# 15_-_LED-User-Debug.net
KiCad netlist of a schematic drawn in Altium Designer
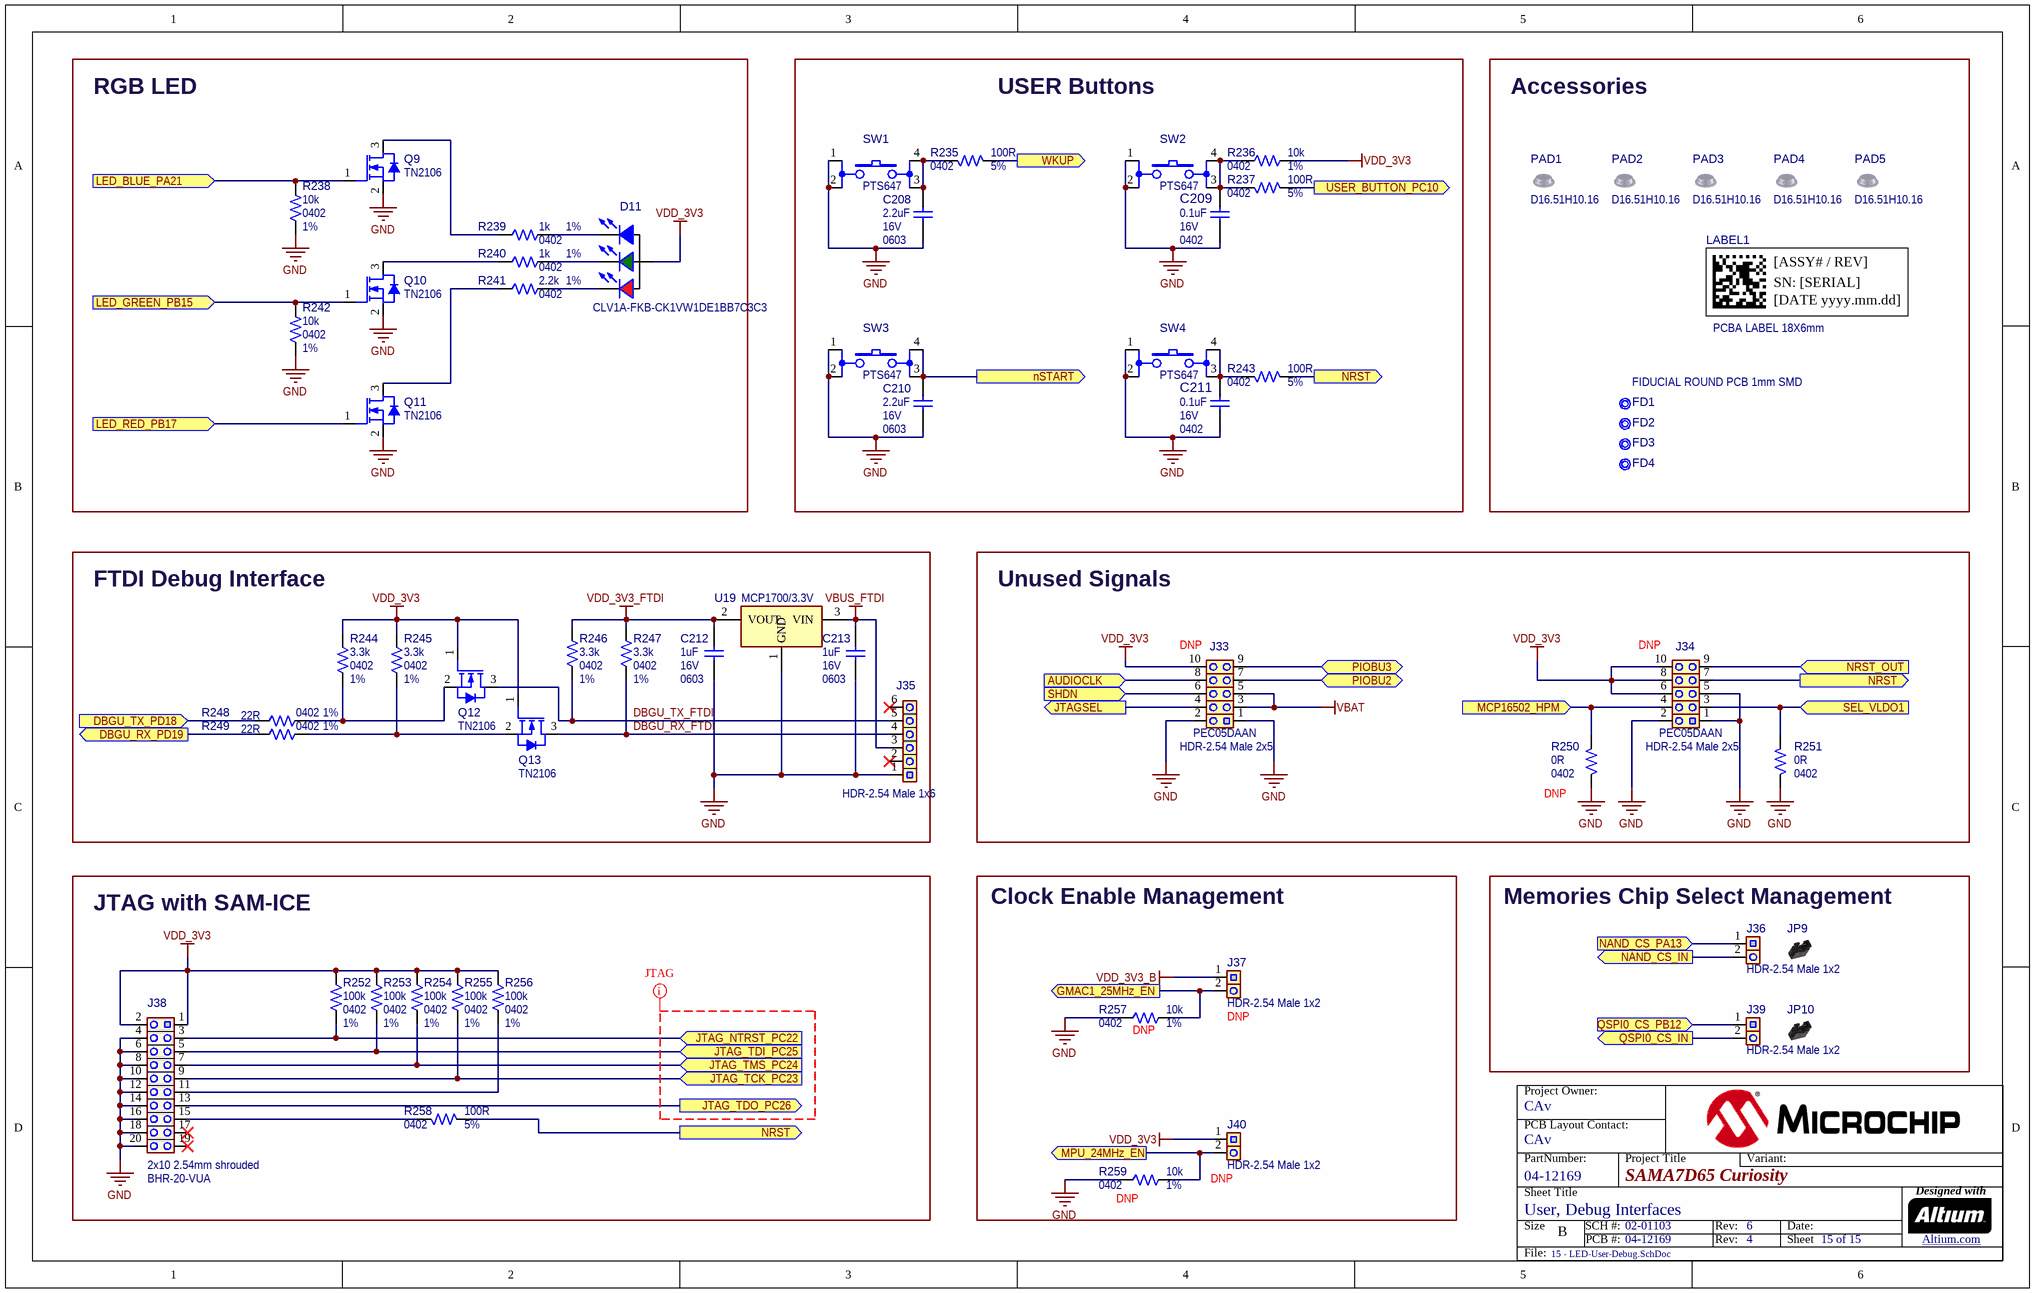
[diagram p0: 15 - LED-User-Debug.SchDoc]

(export (version "E")
  (design (tool "Eeschema 10.0.6"))
  (components
    (comp (ref "C208")
      (value "2.2uF")
      (footprint "CAP_C_0603")
      (fields
        (field (name "VOLTAGE") "16V")
        (field (name "PACKAGE") "0603")
        (field (name "TOLERANCE") "10%")
        (field (name "Comment") "Capacitor NP")
      )
      (libsource (lib "MCHP-CDB") (part "Capacitor NP"))
    )
    (comp (ref "C209")
      (value "0.1uF")
      (footprint "CAP_C_0402")
      (fields
        (field (name "VOLTAGE") "16V")
        (field (name "PACKAGE") "0402")
        (field (name "TOLERANCE") "10%")
        (field (name "Comment") "Capacitor NP")
        (field (name "OWNER") "Sompoch Loboonlert")
      )
      (libsource (lib "MCHP-CDB") (part "Capacitor NP"))
    )
    (comp (ref "C210")
      (value "2.2uF")
      (footprint "CAP_C_0603")
      (fields
        (field (name "VOLTAGE") "16V")
        (field (name "PACKAGE") "0603")
        (field (name "TOLERANCE") "10%")
        (field (name "Comment") "Capacitor NP")
      )
      (libsource (lib "MCHP-CDB") (part "Capacitor NP"))
    )
    (comp (ref "C211")
      (value "0.1uF")
      (footprint "CAP_C_0402")
      (fields
        (field (name "VOLTAGE") "16V")
        (field (name "PACKAGE") "0402")
        (field (name "TOLERANCE") "10%")
        (field (name "Comment") "Capacitor NP")
        (field (name "OWNER") "Sompoch Loboonlert")
      )
      (libsource (lib "MCHP-CDB") (part "Capacitor NP"))
    )
    (comp (ref "C212")
      (value "1uF")
      (footprint "CAP_C_0603")
      (fields
        (field (name "VOLTAGE") "16V")
        (field (name "PACKAGE") "0603")
        (field (name "TOLERANCE") "10%")
        (field (name "Comment") "Capacitor NP")
      )
      (libsource (lib "MCHP-CDB") (part "Capacitor NP"))
    )
    (comp (ref "C213")
      (value "1uF")
      (footprint "CAP_C_0603")
      (fields
        (field (name "VOLTAGE") "16V")
        (field (name "PACKAGE") "0603")
        (field (name "TOLERANCE") "10%")
        (field (name "Comment") "Capacitor NP")
      )
      (libsource (lib "MCHP-CDB") (part "Capacitor NP"))
    )
    (comp (ref "D11")
      (value "LED_RGB_CLV1A")
      (footprint "PLCC-4_CLV1A-FKB")
      (fields
        (field (name "POWER") "130mW, 100mW, 100mW")
        (field (name "MANUFACTURER PART NUMBER 1") "CLV1A-FKB-CK1VW1DE1BB7C3C3")
        (field (name "OWNER") "Randolph Sobrepena")
      )
      (libsource (lib "MCHP-CDB") (part "LED_RGB_CLV1A"))
    )
    (comp (ref "FD1")
      (value "FIDUCIAL ROUND")
      (footprint "Fiducial_1mm")
      (description "Fiducial")
      (fields
        (field (name "DESCRIPTION_") "FIDUCIAL ROUND PCB 1mm SMD")
        (field (name "OWNER") "Dragos Danaila")
      )
      (libsource (lib "MCHP-CDB") (part "FIDUCIAL ROUND"))
    )
    (comp (ref "FD2")
      (value "FIDUCIAL ROUND")
      (footprint "Fiducial_1mm")
      (description "Fiducial")
      (fields (field (name "OWNER") "Dragos Danaila"))
      (libsource (lib "MCHP-CDB") (part "FIDUCIAL ROUND"))
    )
    (comp (ref "FD3")
      (value "FIDUCIAL ROUND")
      (footprint "Fiducial_1mm")
      (description "Fiducial")
      (fields (field (name "OWNER") "Dragos Danaila"))
      (libsource (lib "MCHP-CDB") (part "FIDUCIAL ROUND"))
    )
    (comp (ref "FD4")
      (value "FIDUCIAL ROUND")
      (footprint "Fiducial_1mm")
      (description "Fiducial")
      (fields (field (name "OWNER") "Dragos Danaila"))
      (libsource (lib "MCHP-CDB") (part "FIDUCIAL ROUND"))
    )
    (comp (ref "J33")
      (value "HDR-2.54 Male 2x5")
      (footprint "HDR_M_2.54_2x5")
      (fields
        (field (name "MANUFACTURER PART NUMBER 1") "PEC05DAAN")
        (field (name "POPULATED") "DNP")
        (field (name "Comment") "Header 2x5")
        (field (name "OWNER") "Mike Sullivan (Arena)")
      )
      (libsource (lib "MCHP-CDB") (part "Header 2x5"))
    )
    (comp (ref "J34")
      (value "HDR-2.54 Male 2x5")
      (footprint "HDR_M_2.54_2x5")
      (fields
        (field (name "MANUFACTURER PART NUMBER 1") "PEC05DAAN")
        (field (name "POPULATED") "DNP")
        (field (name "Comment") "Header 2x5")
        (field (name "OWNER") "Mike Sullivan (Arena)")
      )
      (libsource (lib "MCHP-CDB") (part "Header 2x5"))
    )
    (comp (ref "J35")
      (value "HDR-2.54 Male 1x6")
      (footprint "HDR_M_2.54_1x6")
      (fields (field (name "Comment") "Header 1x6") (field (name "OWNER") "Bogdan P (M91398)"))
      (libsource (lib "MCHP-CDB") (part "Header 1x6"))
    )
    (comp (ref "J36")
      (value "HDR-2.54 Male 1x2")
      (footprint "HDR_M_2.54_1x2")
      (fields
        (field (name "VOLTAGE") "250V")
        (field (name "Comment") "Header 1x2")
        (field (name "OWNER") "Narasimha Murthy")
      )
      (libsource (lib "MCHP-CDB") (part "Header 1x2"))
    )
    (comp (ref "J37")
      (value "HDR-2.54 Male 1x2")
      (footprint "HDR_M_2.54_1x2")
      (fields
        (field (name "POPULATED") "DNP")
        (field (name "VOLTAGE") "250V")
        (field (name "Comment") "Header 1x2")
        (field (name "OWNER") "Narasimha Murthy")
      )
      (libsource (lib "MCHP-CDB") (part "Header 1x2"))
    )
    (comp (ref "J38")
      (value "2x10 2.54mm shrouded")
      (footprint "HDR_M_2.54_2X10_SBH11-PBPC-D10-ST-BK")
      (fields
        (field (name "MANUFACTURER PART NUMBER 1") "BHR-20-VUA")
        (field (name "VOLTAGE") "250VAC")
        (field (name "Comment") "Header 2x10")
        (field (name "OWNER") "Dragos Danaila")
      )
      (libsource (lib "MCHP-CDB") (part "Header 2x10"))
    )
    (comp (ref "J39")
      (value "HDR-2.54 Male 1x2")
      (footprint "HDR_M_2.54_1x2")
      (fields
        (field (name "VOLTAGE") "250V")
        (field (name "Comment") "Header 1x2")
        (field (name "OWNER") "Narasimha Murthy")
      )
      (libsource (lib "MCHP-CDB") (part "Header 1x2"))
    )
    (comp (ref "J40")
      (value "HDR-2.54 Male 1x2")
      (footprint "HDR_M_2.54_1x2")
      (fields
        (field (name "POPULATED") "DNP")
        (field (name "VOLTAGE") "250V")
        (field (name "Comment") "Header 1x2")
        (field (name "OWNER") "Narasimha Murthy")
      )
      (libsource (lib "MCHP-CDB") (part "Header 1x2"))
    )
    (comp (ref "JP9")
      (value "Jumper Mechanical")
      (footprint "Jumper_Mechanical")
      (fields (field (name "OWNER") "Narasimha Murthy"))
      (libsource (lib "MCHP-CDB") (part "Jumper Mechanical"))
    )
    (comp (ref "JP10")
      (value "Jumper Mechanical")
      (footprint "Jumper_Mechanical")
      (fields (field (name "OWNER") "Narasimha Murthy"))
      (libsource (lib "MCHP-CDB") (part "Jumper Mechanical"))
    )
    (comp (ref "LABEL1")
      (value "PCBA LABEL 18X6mm")
      (footprint "08-10015")
      (fields (field (name "Comment") "08-10015") (field (name "OWNER") "Mark Loper"))
      (libsource (lib "MCHP-CDB") (part "08-10015"))
    )
    (comp (ref "PAD1")
      (value "D16.51H10.16")
      (footprint "BUMP_BUMPERSPECIALTIES_BS11BL04X08RP_CYLINDRICAL_BLACK_D16.51H10.16")
      (fields (field (name "Comment") "Rubber Pad Cylindrical Taper") (field (name "OWNER") "Dragos Danaila"))
      (libsource (lib "MCHP-CDB") (part "Rubber Pad Cylindrical Taper"))
    )
    (comp (ref "PAD2")
      (value "D16.51H10.16")
      (footprint "BUMP_BUMPERSPECIALTIES_BS11BL04X08RP_CYLINDRICAL_BLACK_D16.51H10.16")
      (fields (field (name "Comment") "Rubber Pad Cylindrical Taper") (field (name "OWNER") "Dragos Danaila"))
      (libsource (lib "MCHP-CDB") (part "Rubber Pad Cylindrical Taper"))
    )
    (comp (ref "PAD3")
      (value "D16.51H10.16")
      (footprint "BUMP_BUMPERSPECIALTIES_BS11BL04X08RP_CYLINDRICAL_BLACK_D16.51H10.16")
      (fields (field (name "Comment") "Rubber Pad Cylindrical Taper") (field (name "OWNER") "Dragos Danaila"))
      (libsource (lib "MCHP-CDB") (part "Rubber Pad Cylindrical Taper"))
    )
    (comp (ref "PAD4")
      (value "D16.51H10.16")
      (footprint "BUMP_BUMPERSPECIALTIES_BS11BL04X08RP_CYLINDRICAL_BLACK_D16.51H10.16")
      (fields (field (name "Comment") "Rubber Pad Cylindrical Taper") (field (name "OWNER") "Dragos Danaila"))
      (libsource (lib "MCHP-CDB") (part "Rubber Pad Cylindrical Taper"))
    )
    (comp (ref "PAD5")
      (value "D16.51H10.16")
      (footprint "BUMP_BUMPERSPECIALTIES_BS11BL04X08RP_CYLINDRICAL_BLACK_D16.51H10.16")
      (fields (field (name "Comment") "Rubber Pad Cylindrical Taper") (field (name "OWNER") "Dragos Danaila"))
      (libsource (lib "MCHP-CDB") (part "Rubber Pad Cylindrical Taper"))
    )
    (comp (ref "Q9")
      (value "TN2106")
      (footprint "SOT-23-3")
      (description "Transistor MOS")
      (fields (field (name "Comment") "Transistor MOS-N GSD") (field (name "OWNER") "Ilie Galan"))
      (libsource (lib "MCHP-CDB") (part "Transistor MOS-N GSD"))
    )
    (comp (ref "Q10")
      (value "TN2106")
      (footprint "SOT-23-3")
      (description "Transistor MOS")
      (fields (field (name "Comment") "Transistor MOS-N GSD") (field (name "OWNER") "Ilie Galan"))
      (libsource (lib "MCHP-CDB") (part "Transistor MOS-N GSD"))
    )
    (comp (ref "Q11")
      (value "TN2106")
      (footprint "SOT-23-3")
      (description "Transistor MOS")
      (fields (field (name "Comment") "Transistor MOS-N GSD") (field (name "OWNER") "Ilie Galan"))
      (libsource (lib "MCHP-CDB") (part "Transistor MOS-N GSD"))
    )
    (comp (ref "Q12")
      (value "TN2106")
      (footprint "SOT-23-3")
      (description "Transistor MOS")
      (fields (field (name "Comment") "Transistor MOS-N GSD") (field (name "OWNER") "Ilie Galan"))
      (libsource (lib "MCHP-CDB") (part "Transistor MOS-N GSD"))
    )
    (comp (ref "Q13")
      (value "TN2106")
      (footprint "SOT-23-3")
      (description "Transistor MOS")
      (fields (field (name "Comment") "Transistor MOS-N GSD") (field (name "OWNER") "Ilie Galan"))
      (libsource (lib "MCHP-CDB") (part "Transistor MOS-N GSD"))
    )
    (comp (ref "R235")
      (value "100R")
      (footprint "RES_C_0402")
      (description "Resistor")
      (fields
        (field (name "PACKAGE") "0402")
        (field (name "TOLERANCE") "5%")
        (field (name "VOLTAGE") "50V")
        (field (name "POWER") "1/16W")
        (field (name "OWNER") "Dragos Danaila")
      )
      (libsource (lib "MCHP-CDB") (part "Resistor"))
    )
    (comp (ref "R236")
      (value "10k")
      (footprint "RES_C_0402")
      (description "Resistor")
      (fields
        (field (name "PACKAGE") "0402")
        (field (name "TOLERANCE") "1%")
        (field (name "POWER") "1/10W")
        (field (name "VOLTAGE") "50V")
        (field (name "OWNER") "Brent Lanphear")
      )
      (libsource (lib "MCHP-CDB") (part "Resistor"))
    )
    (comp (ref "R237")
      (value "100R")
      (footprint "RES_C_0402")
      (description "Resistor")
      (fields
        (field (name "PACKAGE") "0402")
        (field (name "TOLERANCE") "5%")
        (field (name "VOLTAGE") "50V")
        (field (name "POWER") "1/16W")
        (field (name "OWNER") "Dragos Danaila")
      )
      (libsource (lib "MCHP-CDB") (part "Resistor"))
    )
    (comp (ref "R238")
      (value "10k")
      (footprint "RES_C_0402")
      (description "Resistor")
      (fields
        (field (name "PACKAGE") "0402")
        (field (name "TOLERANCE") "1%")
        (field (name "POWER") "1/10W")
        (field (name "VOLTAGE") "50V")
        (field (name "OWNER") "Brent Lanphear")
      )
      (libsource (lib "MCHP-CDB") (part "Resistor"))
    )
    (comp (ref "R239")
      (value "1k")
      (footprint "RES_C_0402")
      (description "Resistor")
      (fields
        (field (name "PACKAGE") "0402")
        (field (name "TOLERANCE") "1%")
        (field (name "VOLTAGE") "50V")
        (field (name "POWER") "1/10W")
        (field (name "OWNER") "Tad Ahlvers")
      )
      (libsource (lib "") (part "Resistor_1"))
    )
    (comp (ref "R240")
      (value "1k")
      (footprint "RES_C_0402")
      (description "Resistor")
      (fields
        (field (name "PACKAGE") "0402")
        (field (name "TOLERANCE") "1%")
        (field (name "VOLTAGE") "50V")
        (field (name "POWER") "1/10W")
        (field (name "OWNER") "Tad Ahlvers")
      )
      (libsource (lib "") (part "Resistor_1"))
    )
    (comp (ref "R241")
      (value "2.2k")
      (footprint "RES_C_0402")
      (description "Resistor")
      (fields
        (field (name "PACKAGE") "0402")
        (field (name "TOLERANCE") "1%")
        (field (name "VOLTAGE") "50V")
        (field (name "POWER") "1/10W")
        (field (name "OWNER") "Tad Ahlvers")
      )
      (libsource (lib "MCHP-CDB") (part "Resistor"))
    )
    (comp (ref "R242")
      (value "10k")
      (footprint "RES_C_0402")
      (description "Resistor")
      (fields
        (field (name "PACKAGE") "0402")
        (field (name "TOLERANCE") "1%")
        (field (name "POWER") "1/10W")
        (field (name "VOLTAGE") "50V")
        (field (name "OWNER") "Brent Lanphear")
      )
      (libsource (lib "MCHP-CDB") (part "Resistor"))
    )
    (comp (ref "R243")
      (value "100R")
      (footprint "RES_C_0402")
      (description "Resistor")
      (fields
        (field (name "PACKAGE") "0402")
        (field (name "TOLERANCE") "5%")
        (field (name "VOLTAGE") "50V")
        (field (name "POWER") "1/16W")
        (field (name "OWNER") "Dragos Danaila")
      )
      (libsource (lib "MCHP-CDB") (part "Resistor"))
    )
    (comp (ref "R244")
      (value "3.3k")
      (footprint "RES_C_0402")
      (description "Resistor")
      (fields
        (field (name "PACKAGE") "0402")
        (field (name "TOLERANCE") "1%")
        (field (name "VOLTAGE") "50V")
        (field (name "POWER") "1/10W")
        (field (name "OWNER") "Mike Ragsdale")
      )
      (libsource (lib "MCHP-CDB") (part "Resistor"))
    )
    (comp (ref "R245")
      (value "3.3k")
      (footprint "RES_C_0402")
      (description "Resistor")
      (fields
        (field (name "PACKAGE") "0402")
        (field (name "TOLERANCE") "1%")
        (field (name "VOLTAGE") "50V")
        (field (name "POWER") "1/10W")
        (field (name "OWNER") "Mike Ragsdale")
      )
      (libsource (lib "MCHP-CDB") (part "Resistor"))
    )
    (comp (ref "R246")
      (value "3.3k")
      (footprint "RES_C_0402")
      (description "Resistor")
      (fields
        (field (name "PACKAGE") "0402")
        (field (name "TOLERANCE") "1%")
        (field (name "VOLTAGE") "50V")
        (field (name "POWER") "1/10W")
        (field (name "OWNER") "Mike Ragsdale")
      )
      (libsource (lib "MCHP-CDB") (part "Resistor"))
    )
    (comp (ref "R247")
      (value "3.3k")
      (footprint "RES_C_0402")
      (description "Resistor")
      (fields
        (field (name "PACKAGE") "0402")
        (field (name "TOLERANCE") "1%")
        (field (name "VOLTAGE") "50V")
        (field (name "POWER") "1/10W")
        (field (name "OWNER") "Mike Ragsdale")
      )
      (libsource (lib "MCHP-CDB") (part "Resistor"))
    )
    (comp (ref "R248")
      (value "22R")
      (footprint "RES_C_0402")
      (description "Resistor")
      (fields
        (field (name "PACKAGE") "0402")
        (field (name "TOLERANCE") "1%")
        (field (name "POWER") "1/10W")
        (field (name "OWNER") "Mike Ragsdale")
      )
      (libsource (lib "MCHP-CDB") (part "Resistor"))
    )
    (comp (ref "R249")
      (value "22R")
      (footprint "RES_C_0402")
      (description "Resistor")
      (fields
        (field (name "PACKAGE") "0402")
        (field (name "TOLERANCE") "1%")
        (field (name "POWER") "1/10W")
        (field (name "OWNER") "Mike Ragsdale")
      )
      (libsource (lib "MCHP-CDB") (part "Resistor"))
    )
    (comp (ref "R250")
      (value "0R")
      (footprint "RES_C_0402")
      (description "Resistor")
      (fields
        (field (name "PACKAGE") "0402")
        (field (name "POWER") "1/16W")
        (field (name "POPULATED") "DNP")
        (field (name "OWNER") "Sompoch Loboonlert")
      )
      (libsource (lib "") (part "Resistor_1"))
    )
    (comp (ref "R251")
      (value "0R")
      (footprint "RES_C_0402")
      (description "Resistor")
      (fields
        (field (name "PACKAGE") "0402")
        (field (name "POWER") "1/16W")
        (field (name "OWNER") "Sompoch Loboonlert")
      )
      (libsource (lib "") (part "Resistor_1"))
    )
    (comp (ref "R252")
      (value "100k")
      (footprint "RES_C_0402")
      (description "Resistor")
      (fields
        (field (name "PACKAGE") "0402")
        (field (name "TOLERANCE") "1%")
        (field (name "VOLTAGE") "50V")
        (field (name "POWER") "1/10W")
        (field (name "OWNER") "Tad Ahlvers")
      )
      (libsource (lib "MCHP-CDB") (part "Resistor"))
    )
    (comp (ref "R253")
      (value "100k")
      (footprint "RES_C_0402")
      (description "Resistor")
      (fields
        (field (name "PACKAGE") "0402")
        (field (name "TOLERANCE") "1%")
        (field (name "VOLTAGE") "50V")
        (field (name "POWER") "1/10W")
        (field (name "OWNER") "Tad Ahlvers")
      )
      (libsource (lib "MCHP-CDB") (part "Resistor"))
    )
    (comp (ref "R254")
      (value "100k")
      (footprint "RES_C_0402")
      (description "Resistor")
      (fields
        (field (name "PACKAGE") "0402")
        (field (name "TOLERANCE") "1%")
        (field (name "VOLTAGE") "50V")
        (field (name "POWER") "1/10W")
        (field (name "OWNER") "Tad Ahlvers")
      )
      (libsource (lib "MCHP-CDB") (part "Resistor"))
    )
    (comp (ref "R255")
      (value "100k")
      (footprint "RES_C_0402")
      (description "Resistor")
      (fields
        (field (name "PACKAGE") "0402")
        (field (name "TOLERANCE") "1%")
        (field (name "VOLTAGE") "50V")
        (field (name "POWER") "1/10W")
        (field (name "OWNER") "Tad Ahlvers")
      )
      (libsource (lib "MCHP-CDB") (part "Resistor"))
    )
    (comp (ref "R256")
      (value "100k")
      (footprint "RES_C_0402")
      (description "Resistor")
      (fields
        (field (name "PACKAGE") "0402")
        (field (name "TOLERANCE") "1%")
        (field (name "VOLTAGE") "50V")
        (field (name "POWER") "1/10W")
        (field (name "OWNER") "Tad Ahlvers")
      )
      (libsource (lib "MCHP-CDB") (part "Resistor"))
    )
    (comp (ref "R257")
      (value "10k")
      (footprint "RES_C_0402")
      (description "Resistor")
      (fields
        (field (name "PACKAGE") "0402")
        (field (name "TOLERANCE") "1%")
        (field (name "VOLTAGE") "50V")
        (field (name "POWER") "1/10W")
        (field (name "POPULATED") "DNP")
        (field (name "OWNER") "Brent Lanphear")
      )
      (libsource (lib "") (part "Resistor_1"))
    )
    (comp (ref "R258")
      (value "100R")
      (footprint "RES_C_0402")
      (description "Resistor")
      (fields
        (field (name "PACKAGE") "0402")
        (field (name "TOLERANCE") "5%")
        (field (name "VOLTAGE") "50V")
        (field (name "POWER") "1/16W")
        (field (name "OWNER") "Dragos Danaila")
      )
      (libsource (lib "MCHP-CDB") (part "Resistor"))
    )
    (comp (ref "R259")
      (value "10k")
      (footprint "RES_C_0402")
      (description "Resistor")
      (fields
        (field (name "PACKAGE") "0402")
        (field (name "TOLERANCE") "1%")
        (field (name "VOLTAGE") "50V")
        (field (name "POWER") "1/10W")
        (field (name "POPULATED") "DNP")
        (field (name "OWNER") "Brent Lanphear")
      )
      (libsource (lib "") (part "Resistor_1"))
    )
    (comp (ref "SW1")
      (value "PTS647")
      (footprint "SW_SMD_4.5mmX4.5mm_PTS647")
      (description "Switch")
      (fields
        (field (name "VOLTAGE") "12V")
        (field (name "Comment") "Switch 4 Pin")
        (field (name "OWNER") "Dragos Danaila")
      )
      (libsource (lib "MCHP-CDB") (part "Switch 4 Pin"))
    )
    (comp (ref "SW2")
      (value "PTS647")
      (footprint "SW_SMD_4.5mmX4.5mm_PTS647")
      (description "Switch")
      (fields
        (field (name "VOLTAGE") "12V")
        (field (name "Comment") "Switch 4 Pin")
        (field (name "OWNER") "Dragos Danaila")
      )
      (libsource (lib "MCHP-CDB") (part "Switch 4 Pin"))
    )
    (comp (ref "SW3")
      (value "PTS647")
      (footprint "SW_SMD_4.5mmX4.5mm_PTS647")
      (description "Switch")
      (fields
        (field (name "VOLTAGE") "12V")
        (field (name "Comment") "Switch 4 Pin")
        (field (name "OWNER") "Dragos Danaila")
      )
      (libsource (lib "MCHP-CDB") (part "Switch 4 Pin"))
    )
    (comp (ref "SW4")
      (value "PTS647")
      (footprint "SW_SMD_4.5mmX4.5mm_PTS647")
      (description "Switch")
      (fields
        (field (name "VOLTAGE") "12V")
        (field (name "Comment") "Switch 4 Pin")
        (field (name "OWNER") "Dragos Danaila")
      )
      (libsource (lib "MCHP-CDB") (part "Switch 4 Pin"))
    )
    (comp (ref "U19")
      (value "MCP1700/3.3V")
      (footprint "SOT-23-3")
      (description "LDO")
      (fields (field (name "Comment") "MCP170X SOT-23-3_SOT-23A-3"))
      (libsource (lib "MCHP-CDB") (part "MCP170X SOT-23-3_SOT-23A-3"))
    )
  )
  (nets
    (net (code "1") (name "/AUDIOCLK") (class "Default")
      (node (ref "J33") (pin "8") (pinfunction "8_8") (pintype "passive"))
    )
    (net (code "2") (name "/DBGU_RX_FTDI") (class "Default")
      (node (ref "J35") (pin "4") (pinfunction "4_4") (pintype "passive"))
      (node (ref "Q13") (pin "3") (pinfunction "D_3") (pintype "passive"))
      (node (ref "R247") (pin "1") (pinfunction "1_1") (pintype "passive"))
    )
    (net (code "3") (name "/DBGU_RX_PD19") (class "Default")
      (node (ref "R249") (pin "1") (pinfunction "1_1") (pintype "passive"))
    )
    (net (code "4") (name "/DBGU_TX_FTDI") (class "Default")
      (node (ref "J35") (pin "5") (pinfunction "5_5") (pintype "passive"))
      (node (ref "Q12") (pin "3") (pinfunction "D_3") (pintype "passive"))
      (node (ref "R246") (pin "1") (pinfunction "1_1") (pintype "passive"))
    )
    (net (code "5") (name "/DBGU_TX_PD18") (class "Default")
      (node (ref "R248") (pin "1") (pinfunction "1_1") (pintype "passive"))
    )
    (net (code "6") (name "/GMAC1_25MHz_EN") (class "Default")
      (node (ref "J37") (pin "2") (pinfunction "2_2") (pintype "passive"))
      (node (ref "R257") (pin "1") (pinfunction "1_1") (pintype "passive"))
    )
    (net (code "7") (name "/JTAGSEL") (class "Default")
      (node (ref "J33") (pin "4") (pinfunction "4_4") (pintype "passive"))
    )
    (net (code "8") (name "/JTAG_NTRST_PC22") (class "Default")
      (node (ref "J38") (pin "3") (pinfunction "3_3") (pintype "passive"))
      (node (ref "R252") (pin "1") (pinfunction "1_1") (pintype "passive"))
    )
    (net (code "9") (name "/JTAG_TCK_PC23") (class "Default")
      (node (ref "J38") (pin "9") (pinfunction "9_9") (pintype "passive"))
      (node (ref "R255") (pin "1") (pinfunction "1_1") (pintype "passive"))
    )
    (net (code "10") (name "/JTAG_TDI_PC25") (class "Default")
      (node (ref "J38") (pin "5") (pinfunction "5_5") (pintype "passive"))
      (node (ref "R253") (pin "1") (pinfunction "1_1") (pintype "passive"))
    )
    (net (code "11") (name "/JTAG_TDO_PC26") (class "Default")
      (node (ref "J38") (pin "13") (pinfunction "13_13") (pintype "passive"))
    )
    (net (code "12") (name "/JTAG_TMS_PC24") (class "Default")
      (node (ref "J38") (pin "7") (pinfunction "7_7") (pintype "passive"))
      (node (ref "R254") (pin "1") (pinfunction "1_1") (pintype "passive"))
    )
    (net (code "13") (name "/LED_BLUE_PA21") (class "Default")
      (node (ref "Q9") (pin "1") (pinfunction "G_1") (pintype "passive"))
      (node (ref "R238") (pin "1") (pinfunction "1_1") (pintype "passive"))
    )
    (net (code "14") (name "/LED_GREEN_PB15") (class "Default")
      (node (ref "Q10") (pin "1") (pinfunction "G_1") (pintype "passive"))
      (node (ref "R242") (pin "1") (pinfunction "1_1") (pintype "passive"))
    )
    (net (code "15") (name "/LED_RED_PB17") (class "Default")
      (node (ref "Q11") (pin "1") (pinfunction "G_1") (pintype "passive"))
    )
    (net (code "16") (name "/MCP16502_HPM") (class "Default")
      (node (ref "J34") (pin "4") (pinfunction "4_4") (pintype "passive"))
      (node (ref "R250") (pin "2") (pinfunction "2_2") (pintype "passive"))
    )
    (net (code "17") (name "/MPU_24MHz_EN") (class "Default")
      (node (ref "J40") (pin "2") (pinfunction "2_2") (pintype "passive"))
      (node (ref "R259") (pin "1") (pinfunction "1_1") (pintype "passive"))
    )
    (net (code "18") (name "/NAND_CS_IN") (class "Default")
      (node (ref "J36") (pin "2") (pinfunction "2_2") (pintype "passive"))
    )
    (net (code "19") (name "/NAND_CS_PA13") (class "Default")
      (node (ref "J36") (pin "1") (pinfunction "1_1") (pintype "passive"))
    )
    (net (code "20") (name "/NRST") (class "Default")
      (node (ref "J34") (pin "7") (pinfunction "7_7") (pintype "passive"))
      (node (ref "R243") (pin "2") (pinfunction "2_2") (pintype "passive"))
      (node (ref "R258") (pin "2") (pinfunction "2_2") (pintype "passive"))
    )
    (net (code "21") (name "/NRST_OUT") (class "Default")
      (node (ref "J34") (pin "9") (pinfunction "9_9") (pintype "passive"))
    )
    (net (code "22") (name "/PIOBU2") (class "Default")
      (node (ref "J33") (pin "7") (pinfunction "7_7") (pintype "passive"))
    )
    (net (code "23") (name "/PIOBU3") (class "Default")
      (node (ref "J33") (pin "9") (pinfunction "9_9") (pintype "passive"))
    )
    (net (code "24") (name "/QSPI0_CS_IN") (class "Default")
      (node (ref "J39") (pin "2") (pinfunction "2_2") (pintype "passive"))
    )
    (net (code "25") (name "/QSPI0_CS_PB12") (class "Default")
      (node (ref "J39") (pin "1") (pinfunction "1_1") (pintype "passive"))
    )
    (net (code "26") (name "/SEL_VLDO1") (class "Default")
      (node (ref "J34") (pin "3") (pinfunction "3_3") (pintype "passive"))
      (node (ref "R251") (pin "2") (pinfunction "2_2") (pintype "passive"))
    )
    (net (code "27") (name "/SHDN") (class "Default")
      (node (ref "J33") (pin "6") (pinfunction "6_6") (pintype "passive"))
    )
    (net (code "28") (name "/USER_BUTTON_PC10") (class "Default")
      (node (ref "R237") (pin "2") (pinfunction "2_2") (pintype "passive"))
    )
    (net (code "29") (name "/WKUP") (class "Default")
      (node (ref "R235") (pin "2") (pinfunction "2_2") (pintype "passive"))
    )
    (net (code "30") (name "/nSTART") (class "Default")
      (node (ref "C210") (pin "2") (pinfunction "2_2") (pintype "passive"))
      (node (ref "SW3") (pin "3") (pinfunction "3_3") (pintype "passive"))
      (node (ref "SW3") (pin "4") (pinfunction "4_4") (pintype "passive"))
    )
    (net (code "31") (name "GND") (class "Default")
      (node (ref "C208") (pin "1") (pinfunction "1_1") (pintype "passive"))
      (node (ref "C209") (pin "1") (pinfunction "1_1") (pintype "passive"))
      (node (ref "C210") (pin "1") (pinfunction "1_1") (pintype "passive"))
      (node (ref "C211") (pin "1") (pinfunction "1_1") (pintype "passive"))
      (node (ref "C212") (pin "1") (pinfunction "1_1") (pintype "passive"))
      (node (ref "C213") (pin "1") (pinfunction "1_1") (pintype "passive"))
      (node (ref "J33") (pin "1") (pinfunction "1_1") (pintype "passive"))
      (node (ref "J33") (pin "2") (pinfunction "2_2") (pintype "passive"))
      (node (ref "J34") (pin "1") (pinfunction "1_1") (pintype "passive"))
      (node (ref "J34") (pin "2") (pinfunction "2_2") (pintype "passive"))
      (node (ref "J34") (pin "5") (pinfunction "5_5") (pintype "passive"))
      (node (ref "J35") (pin "1") (pinfunction "1_1") (pintype "passive"))
      (node (ref "J38") (pin "10") (pinfunction "10_10") (pintype "passive"))
      (node (ref "J38") (pin "12") (pinfunction "12_12") (pintype "passive"))
      (node (ref "J38") (pin "14") (pinfunction "14_14") (pintype "passive"))
      (node (ref "J38") (pin "16") (pinfunction "16_16") (pintype "passive"))
      (node (ref "J38") (pin "18") (pinfunction "18_18") (pintype "passive"))
      (node (ref "J38") (pin "20") (pinfunction "20_20") (pintype "passive"))
      (node (ref "J38") (pin "4") (pinfunction "4_4") (pintype "passive"))
      (node (ref "J38") (pin "6") (pinfunction "6_6") (pintype "passive"))
      (node (ref "J38") (pin "8") (pinfunction "8_8") (pintype "passive"))
      (node (ref "Q10") (pin "2") (pinfunction "S_2") (pintype "passive"))
      (node (ref "Q11") (pin "2") (pinfunction "S_2") (pintype "passive"))
      (node (ref "Q9") (pin "2") (pinfunction "S_2") (pintype "passive"))
      (node (ref "R238") (pin "2") (pinfunction "2_2") (pintype "passive"))
      (node (ref "R242") (pin "2") (pinfunction "2_2") (pintype "passive"))
      (node (ref "R250") (pin "1") (pinfunction "1_1") (pintype "passive"))
      (node (ref "R251") (pin "1") (pinfunction "1_1") (pintype "passive"))
      (node (ref "R257") (pin "2") (pinfunction "2_2") (pintype "passive"))
      (node (ref "R259") (pin "2") (pinfunction "2_2") (pintype "passive"))
      (node (ref "SW1") (pin "1") (pinfunction "1_1") (pintype "passive"))
      (node (ref "SW1") (pin "2") (pinfunction "2_2") (pintype "passive"))
      (node (ref "SW2") (pin "1") (pinfunction "1_1") (pintype "passive"))
      (node (ref "SW2") (pin "2") (pinfunction "2_2") (pintype "passive"))
      (node (ref "SW3") (pin "1") (pinfunction "1_1") (pintype "passive"))
      (node (ref "SW3") (pin "2") (pinfunction "2_2") (pintype "passive"))
      (node (ref "SW4") (pin "1") (pinfunction "1_1") (pintype "passive"))
      (node (ref "SW4") (pin "2") (pinfunction "2_2") (pintype "passive"))
      (node (ref "U19") (pin "1") (pinfunction "GND_1") (pintype "power_in"))
    )
    (net (code "32") (name "Net-(C208-Pad2)") (class "Default")
      (node (ref "C208") (pin "2") (pinfunction "2_2") (pintype "passive"))
      (node (ref "R235") (pin "1") (pinfunction "1_1") (pintype "passive"))
      (node (ref "SW1") (pin "3") (pinfunction "3_3") (pintype "passive"))
      (node (ref "SW1") (pin "4") (pinfunction "4_4") (pintype "passive"))
    )
    (net (code "33") (name "Net-(C209-Pad2)") (class "Default")
      (node (ref "C209") (pin "2") (pinfunction "2_2") (pintype "passive"))
      (node (ref "R236") (pin "1") (pinfunction "1_1") (pintype "passive"))
      (node (ref "R237") (pin "1") (pinfunction "1_1") (pintype "passive"))
      (node (ref "SW2") (pin "3") (pinfunction "3_3") (pintype "passive"))
      (node (ref "SW2") (pin "4") (pinfunction "4_4") (pintype "passive"))
    )
    (net (code "34") (name "Net-(C211-Pad2)") (class "Default")
      (node (ref "C211") (pin "2") (pinfunction "2_2") (pintype "passive"))
      (node (ref "R243") (pin "1") (pinfunction "1_1") (pintype "passive"))
      (node (ref "SW4") (pin "3") (pinfunction "3_3") (pintype "passive"))
      (node (ref "SW4") (pin "4") (pinfunction "4_4") (pintype "passive"))
    )
    (net (code "35") (name "Net-(D11-Kb)") (class "Default")
      (node (ref "D11") (pin "3") (pinfunction "Kb_3") (pintype "passive"))
      (node (ref "R239") (pin "2") (pinfunction "2_2") (pintype "passive"))
    )
    (net (code "36") (name "Net-(D11-Kg)") (class "Default")
      (node (ref "D11") (pin "4") (pinfunction "Kg_4") (pintype "passive"))
      (node (ref "R240") (pin "2") (pinfunction "2_2") (pintype "passive"))
    )
    (net (code "37") (name "Net-(D11-Kr)") (class "Default")
      (node (ref "D11") (pin "1") (pinfunction "Kr_1") (pintype "passive"))
      (node (ref "R241") (pin "2") (pinfunction "2_2") (pintype "passive"))
    )
    (net (code "38") (name "Net-(J38-Pad11)") (class "Default")
      (node (ref "J38") (pin "11") (pinfunction "11_11") (pintype "passive"))
      (node (ref "R256") (pin "1") (pinfunction "1_1") (pintype "passive"))
    )
    (net (code "39") (name "Net-(J38-Pad15)") (class "Default")
      (node (ref "J38") (pin "15") (pinfunction "15_15") (pintype "passive"))
      (node (ref "R258") (pin "1") (pinfunction "1_1") (pintype "passive"))
    )
    (net (code "40") (name "Net-(Q9-D)") (class "Default")
      (node (ref "Q9") (pin "3") (pinfunction "D_3") (pintype "passive"))
      (node (ref "R239") (pin "1") (pinfunction "1_1") (pintype "passive"))
    )
    (net (code "41") (name "Net-(Q10-D)") (class "Default")
      (node (ref "Q10") (pin "3") (pinfunction "D_3") (pintype "passive"))
      (node (ref "R240") (pin "1") (pinfunction "1_1") (pintype "passive"))
    )
    (net (code "42") (name "Net-(Q11-D)") (class "Default")
      (node (ref "Q11") (pin "3") (pinfunction "D_3") (pintype "passive"))
      (node (ref "R241") (pin "1") (pinfunction "1_1") (pintype "passive"))
    )
    (net (code "43") (name "Net-(Q12-S)") (class "Default")
      (node (ref "Q12") (pin "2") (pinfunction "S_2") (pintype "passive"))
      (node (ref "R244") (pin "1") (pinfunction "1_1") (pintype "passive"))
      (node (ref "R248") (pin "2") (pinfunction "2_2") (pintype "passive"))
    )
    (net (code "44") (name "Net-(Q13-S)") (class "Default")
      (node (ref "Q13") (pin "2") (pinfunction "S_2") (pintype "passive"))
      (node (ref "R245") (pin "1") (pinfunction "1_1") (pintype "passive"))
      (node (ref "R249") (pin "2") (pinfunction "2_2") (pintype "passive"))
    )
    (net (code "45") (name "VBAT") (class "Default")
      (node (ref "J33") (pin "3") (pinfunction "3_3") (pintype "passive"))
      (node (ref "J33") (pin "5") (pinfunction "5_5") (pintype "passive"))
    )
    (net (code "46") (name "VBUS_FTDI") (class "Default")
      (node (ref "C213") (pin "2") (pinfunction "2_2") (pintype "passive"))
      (node (ref "J35") (pin "3") (pinfunction "3_3") (pintype "passive"))
      (node (ref "U19") (pin "3") (pinfunction "VIN_3") (pintype "power_in"))
    )
    (net (code "47") (name "VDD_3V3") (class "Default")
      (node (ref "D11") (pin "2") (pinfunction "A_2") (pintype "passive"))
      (node (ref "J33") (pin "10") (pinfunction "10_10") (pintype "passive"))
      (node (ref "J34") (pin "10") (pinfunction "10_10") (pintype "passive"))
      (node (ref "J34") (pin "6") (pinfunction "6_6") (pintype "passive"))
      (node (ref "J34") (pin "8") (pinfunction "8_8") (pintype "passive"))
      (node (ref "J38") (pin "1") (pinfunction "1_1") (pintype "passive"))
      (node (ref "J38") (pin "2") (pinfunction "2_2") (pintype "passive"))
      (node (ref "J40") (pin "1") (pinfunction "1_1") (pintype "passive"))
      (node (ref "Q12") (pin "1") (pinfunction "G_1") (pintype "passive"))
      (node (ref "Q13") (pin "1") (pinfunction "G_1") (pintype "passive"))
      (node (ref "R236") (pin "2") (pinfunction "2_2") (pintype "passive"))
      (node (ref "R244") (pin "2") (pinfunction "2_2") (pintype "passive"))
      (node (ref "R245") (pin "2") (pinfunction "2_2") (pintype "passive"))
      (node (ref "R252") (pin "2") (pinfunction "2_2") (pintype "passive"))
      (node (ref "R253") (pin "2") (pinfunction "2_2") (pintype "passive"))
      (node (ref "R254") (pin "2") (pinfunction "2_2") (pintype "passive"))
      (node (ref "R255") (pin "2") (pinfunction "2_2") (pintype "passive"))
      (node (ref "R256") (pin "2") (pinfunction "2_2") (pintype "passive"))
    )
    (net (code "48") (name "VDD_3V3_B") (class "Default")
      (node (ref "J37") (pin "1") (pinfunction "1_1") (pintype "passive"))
    )
    (net (code "49") (name "VDD_3V3_FTDI") (class "Default")
      (node (ref "C212") (pin "2") (pinfunction "2_2") (pintype "passive"))
      (node (ref "R246") (pin "2") (pinfunction "2_2") (pintype "passive"))
      (node (ref "R247") (pin "2") (pinfunction "2_2") (pintype "passive"))
      (node (ref "U19") (pin "2") (pinfunction "VOUT_2") (pintype "power_in"))
    )
    (net (code "50") (name "unconnected-(FD1-Pad1)") (class "Default")
      (node (ref "FD1") (pin "1") (pinfunction "1_1") (pintype "passive"))
    )
    (net (code "51") (name "unconnected-(FD2-Pad1)") (class "Default")
      (node (ref "FD2") (pin "1") (pinfunction "1_1") (pintype "passive"))
    )
    (net (code "52") (name "unconnected-(FD3-Pad1)") (class "Default")
      (node (ref "FD3") (pin "1") (pinfunction "1_1") (pintype "passive"))
    )
    (net (code "53") (name "unconnected-(FD4-Pad1)") (class "Default")
      (node (ref "FD4") (pin "1") (pinfunction "1_1") (pintype "passive"))
    )
    (net (code "54") (name "unconnected-(J35-Pad2)") (class "Default")
      (node (ref "J35") (pin "2") (pinfunction "2_2") (pintype "passive+no_connect"))
    )
    (net (code "55") (name "unconnected-(J35-Pad6)") (class "Default")
      (node (ref "J35") (pin "6") (pinfunction "6_6") (pintype "passive+no_connect"))
    )
    (net (code "56") (name "unconnected-(J38-Pad17)") (class "Default")
      (node (ref "J38") (pin "17") (pinfunction "17_17") (pintype "passive+no_connect"))
    )
    (net (code "57") (name "unconnected-(J38-Pad19)") (class "Default")
      (node (ref "J38") (pin "19") (pinfunction "19_19") (pintype "passive+no_connect"))
    )
  )
)
